# POWER_SUPPLY.net
KiCad netlist of a schematic drawn in Altium Designer
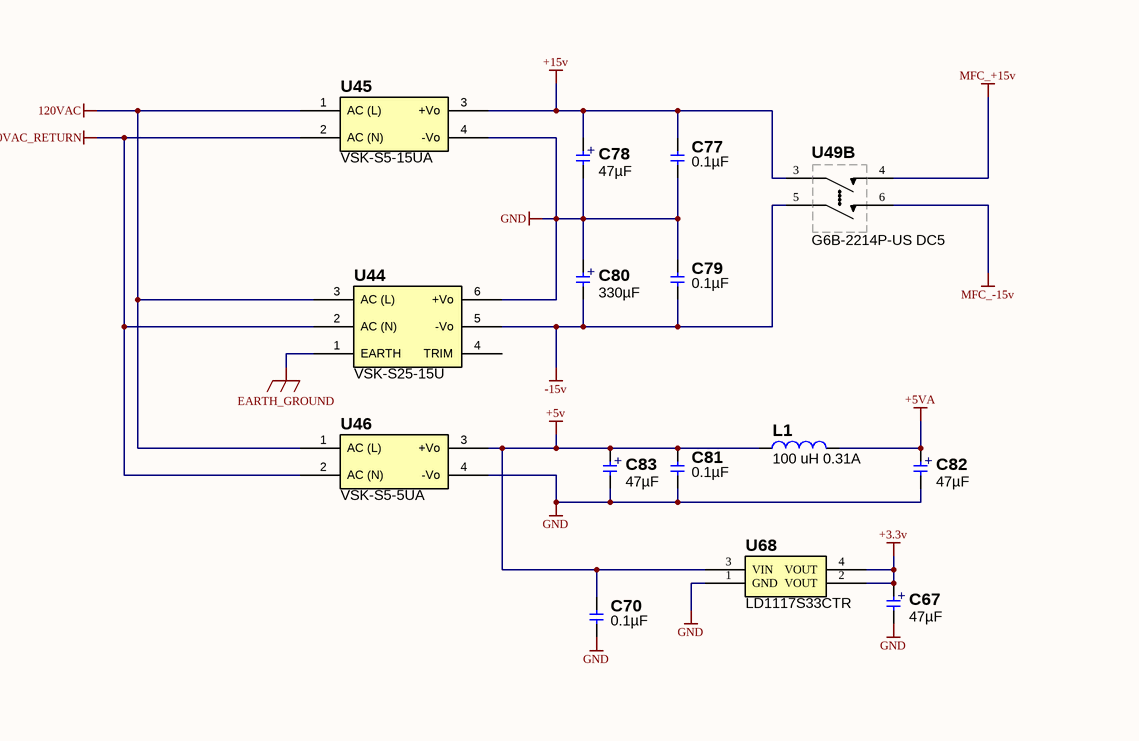
[diagram p0: POWER_SUPPLY.SchDoc, left]
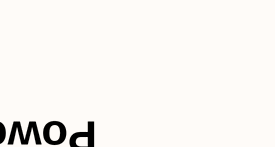
[diagram p1: POWER_SUPPLY.SchDoc, right]

(export (version "E")
  (design (tool "Eeschema 10.0.6"))
  (components
    (comp (ref "C67")
      (value "47µF")
      (footprint "C_ALU_D")
      (description "CAP ALUM 47UF 25V 20% SMD")
      (fields
        (field (name "MANUFACTURER PART NUMBER") "EEE-FK1E470P")
        (field (name "MANUFACTURER") "Panasonic Electronic Components")
      )
      (libsource (lib "Capacitors") (part "C_2P_P"))
    )
    (comp (ref "C70")
      (value "0.1µF")
      (footprint "C0805_LD")
      (description "CAP CER 0.1UF 50V 10% X7R 0805")
      (fields
        (field (name "MANUFACTURER PART NUMBER") "GRM21BR71H104KA01L")
        (field (name "MANUFACTURER") "Murata Electronics North America")
      )
      (libsource (lib "Capacitors") (part "C_2P_NP"))
    )
    (comp (ref "C77")
      (value "0.1µF")
      (footprint "C0805_LD")
      (description "CAP CER 0.1UF 50V 10% X7R 0805")
      (fields
        (field (name "MANUFACTURER PART NUMBER") "GRM21BR71H104KA01L")
        (field (name "MANUFACTURER") "Murata Electronics North America")
      )
      (libsource (lib "Capacitors") (part "C_2P_NP"))
    )
    (comp (ref "C78")
      (value "47µF")
      (footprint "C_ALU_D")
      (description "CAP ALUM 47UF 25V 20% SMD")
      (fields
        (field (name "MANUFACTURER PART NUMBER") "EEE-FK1E470P")
        (field (name "MANUFACTURER") "Panasonic Electronic Components")
      )
      (libsource (lib "Capacitors") (part "C_2P_P"))
    )
    (comp (ref "C79")
      (value "0.1µF")
      (footprint "C0805_LD")
      (description "CAP CER 0.1UF 50V 10% X7R 0805")
      (fields
        (field (name "MANUFACTURER PART NUMBER") "GRM21BR71H104KA01L")
        (field (name "MANUFACTURER") "Murata Electronics North America")
      )
      (libsource (lib "Capacitors") (part "C_2P_NP"))
    )
    (comp (ref "C80")
      (value "330µF")
      (footprint "C_ALU_F")
      (description "CAP ALUM 330UF 25V 20% SMD")
      (fields
        (field (name "MANUFACTURER PART NUMBER") "EEE-FK1E331P")
        (field (name "MANUFACTURER") "Panasonic Electronic Components")
      )
      (libsource (lib "Capacitors") (part "C_2P_P"))
    )
    (comp (ref "C81")
      (value "0.1µF")
      (footprint "C0805_LD")
      (description "CAP CER 0.1UF 50V 10% X7R 0805")
      (fields
        (field (name "MANUFACTURER PART NUMBER") "GRM21BR71H104KA01L")
        (field (name "MANUFACTURER") "Murata Electronics North America")
      )
      (libsource (lib "Capacitors") (part "C_2P_NP"))
    )
    (comp (ref "C82")
      (value "47µF")
      (footprint "C_ALU_D")
      (description "CAP ALUM 47UF 25V 20% SMD")
      (fields
        (field (name "MANUFACTURER PART NUMBER") "EEE-FK1E470P")
        (field (name "MANUFACTURER") "Panasonic Electronic Components")
      )
      (libsource (lib "Capacitors") (part "C_2P_P"))
    )
    (comp (ref "C83")
      (value "47µF")
      (footprint "C_ALU_D")
      (description "CAP ALUM 47UF 25V 20% SMD")
      (fields
        (field (name "MANUFACTURER PART NUMBER") "EEE-FK1E470P")
        (field (name "MANUFACTURER") "Panasonic Electronic Components")
      )
      (libsource (lib "Capacitors") (part "C_2P_P"))
    )
    (comp (ref "L1")
      (value "100 uH 0.31A")
      (footprint "L_DO1608C")
      (fields
        (field (name "MANUFACTURER PART NUMBER") "DO1608C-104_L")
        (field (name "MANUFACTURER") "Coilcraft")
        (field (name "PART NUMBER") "DO1608C-104_L_")
      )
      (libsource (lib "Inductors") (part "L_2P"))
    )
    (comp (ref "U44")
      (value "VSK-S25-15U")
      (footprint "VSK-S25")
      (description "CONV AC/DC 25W 15V 1.6A PCB")
      (fields (field (name "MANUFACTURER") "CUI Inc"))
      (libsource (lib "eModule") (part "VSK-S25-15U"))
    )
    (comp (ref "U45")
      (value "VSK-S5-15UA")
      (footprint "VSK-S5")
      (description "CONV AC/DC 5W 15V 0.33A PCB")
      (fields (field (name "MANUFACTURER") "CUI Inc"))
      (libsource (lib "eModule") (part "VSK-S5-15UA"))
    )
    (comp (ref "U46")
      (value "VSK-S5-5UA")
      (footprint "VSK-S5")
      (description "CONV AC/DC 5W 5V 1A PCB")
      (fields (field (name "MANUFACTURER") "CUI Inc"))
      (libsource (lib "eModule") (part "VSK-S5-5UA"))
    )
    (comp (ref "U49")
      (value "G6B-2214P-US DC5")
      (footprint "G6B-2214P-US")
      (description "RELAY GENERAL PURPOSE DPST 5A 5V")
      (fields (field (name "MANUFACTURER") "Omron Electronics Inc-EMC Div"))
      (libsource (lib "eElectroMechanical") (part "G6B-2214P-US DC5"))
    )
    (comp (ref "U68")
      (value "LD1117S33CTR")
      (footprint "SOT223")
      (description "IC REG LDO 3.3V 950MA SOT-223")
      (fields (field (name "MANUFACTURER") "STMicroelectronics"))
      (libsource (lib "eIC") (part "LD1117S33CTR"))
    )
  )
  (nets
    (net (code "1") (name "+3.3v") (class "Default")
      (node (ref "C67") (pin "1") (pinfunction "1_1") (pintype "passive"))
      (node (ref "U68") (pin "2") (pinfunction "VOUT_2") (pintype "passive"))
      (node (ref "U68") (pin "4") (pinfunction "VOUT_4") (pintype "passive"))
    )
    (net (code "2") (name "+5VA") (class "Default")
      (node (ref "C82") (pin "1") (pinfunction "1_1") (pintype "passive"))
      (node (ref "L1") (pin "2") (pinfunction "2_2") (pintype "passive"))
    )
    (net (code "3") (name "+5v") (class "Default")
      (node (ref "C70") (pin "2") (pinfunction "2_2") (pintype "passive"))
      (node (ref "C81") (pin "2") (pinfunction "2_2") (pintype "passive"))
      (node (ref "C83") (pin "1") (pinfunction "1_1") (pintype "passive"))
      (node (ref "L1") (pin "1") (pinfunction "1_1") (pintype "passive"))
      (node (ref "U46") (pin "3") (pinfunction "+Vo_3") (pintype "passive"))
      (node (ref "U68") (pin "3") (pinfunction "VIN_3") (pintype "passive"))
    )
    (net (code "4") (name "+15v") (class "Default")
      (node (ref "C77") (pin "2") (pinfunction "2_2") (pintype "passive"))
      (node (ref "C78") (pin "1") (pinfunction "1_1") (pintype "passive"))
      (node (ref "U45") (pin "3") (pinfunction "+Vo_3") (pintype "passive"))
      (node (ref "U49") (pin "3") (pinfunction "3_3") (pintype "passive"))
    )
    (net (code "5") (name "-15v") (class "Default")
      (node (ref "C79") (pin "1") (pinfunction "1_1") (pintype "passive"))
      (node (ref "C80") (pin "2") (pinfunction "2_2") (pintype "passive"))
      (node (ref "U44") (pin "5") (pinfunction "-Vo_5") (pintype "passive"))
      (node (ref "U49") (pin "5") (pinfunction "5_5") (pintype "passive"))
    )
    (net (code "6") (name "120VAC") (class "Default")
      (node (ref "U44") (pin "3") (pinfunction "AC_(L)_3") (pintype "passive"))
      (node (ref "U45") (pin "1") (pinfunction "AC_(L)_1") (pintype "passive"))
      (node (ref "U46") (pin "1") (pinfunction "AC_(L)_1") (pintype "passive"))
    )
    (net (code "7") (name "120VAC_RETURN") (class "Default")
      (node (ref "U44") (pin "2") (pinfunction "AC_(N)_2") (pintype "passive"))
      (node (ref "U45") (pin "2") (pinfunction "AC_(N)_2") (pintype "passive"))
      (node (ref "U46") (pin "2") (pinfunction "AC_(N)_2") (pintype "passive"))
    )
    (net (code "8") (name "EARTH_GROUND") (class "Default")
      (node (ref "U44") (pin "1") (pinfunction "EARTH_1") (pintype "passive"))
    )
    (net (code "9") (name "GND") (class "Default")
      (node (ref "C67") (pin "2") (pinfunction "2_2") (pintype "passive"))
      (node (ref "C70") (pin "1") (pinfunction "1_1") (pintype "passive"))
      (node (ref "C77") (pin "1") (pinfunction "1_1") (pintype "passive"))
      (node (ref "C78") (pin "2") (pinfunction "2_2") (pintype "passive"))
      (node (ref "C79") (pin "2") (pinfunction "2_2") (pintype "passive"))
      (node (ref "C80") (pin "1") (pinfunction "1_1") (pintype "passive"))
      (node (ref "C81") (pin "1") (pinfunction "1_1") (pintype "passive"))
      (node (ref "C82") (pin "2") (pinfunction "2_2") (pintype "passive"))
      (node (ref "C83") (pin "2") (pinfunction "2_2") (pintype "passive"))
      (node (ref "U44") (pin "6") (pinfunction "+Vo_6") (pintype "passive"))
      (node (ref "U45") (pin "4") (pinfunction "-Vo_4") (pintype "passive"))
      (node (ref "U46") (pin "4") (pinfunction "-Vo_4") (pintype "passive"))
      (node (ref "U68") (pin "1") (pinfunction "GND_1") (pintype "passive"))
    )
    (net (code "10") (name "MFC_+15v") (class "Default")
      (node (ref "U49") (pin "4") (pinfunction "4_4") (pintype "passive"))
    )
    (net (code "11") (name "MFC_-15v") (class "Default")
      (node (ref "U49") (pin "6") (pinfunction "6_6") (pintype "passive"))
    )
    (net (code "12") (name "unconnected-(U44-TRIM-Pad4)") (class "Default")
      (node (ref "U44") (pin "4") (pinfunction "TRIM_4") (pintype "passive"))
    )
  )
)
